# Esquematico.net
KiCad netlist of a schematic drawn in Altium Designer
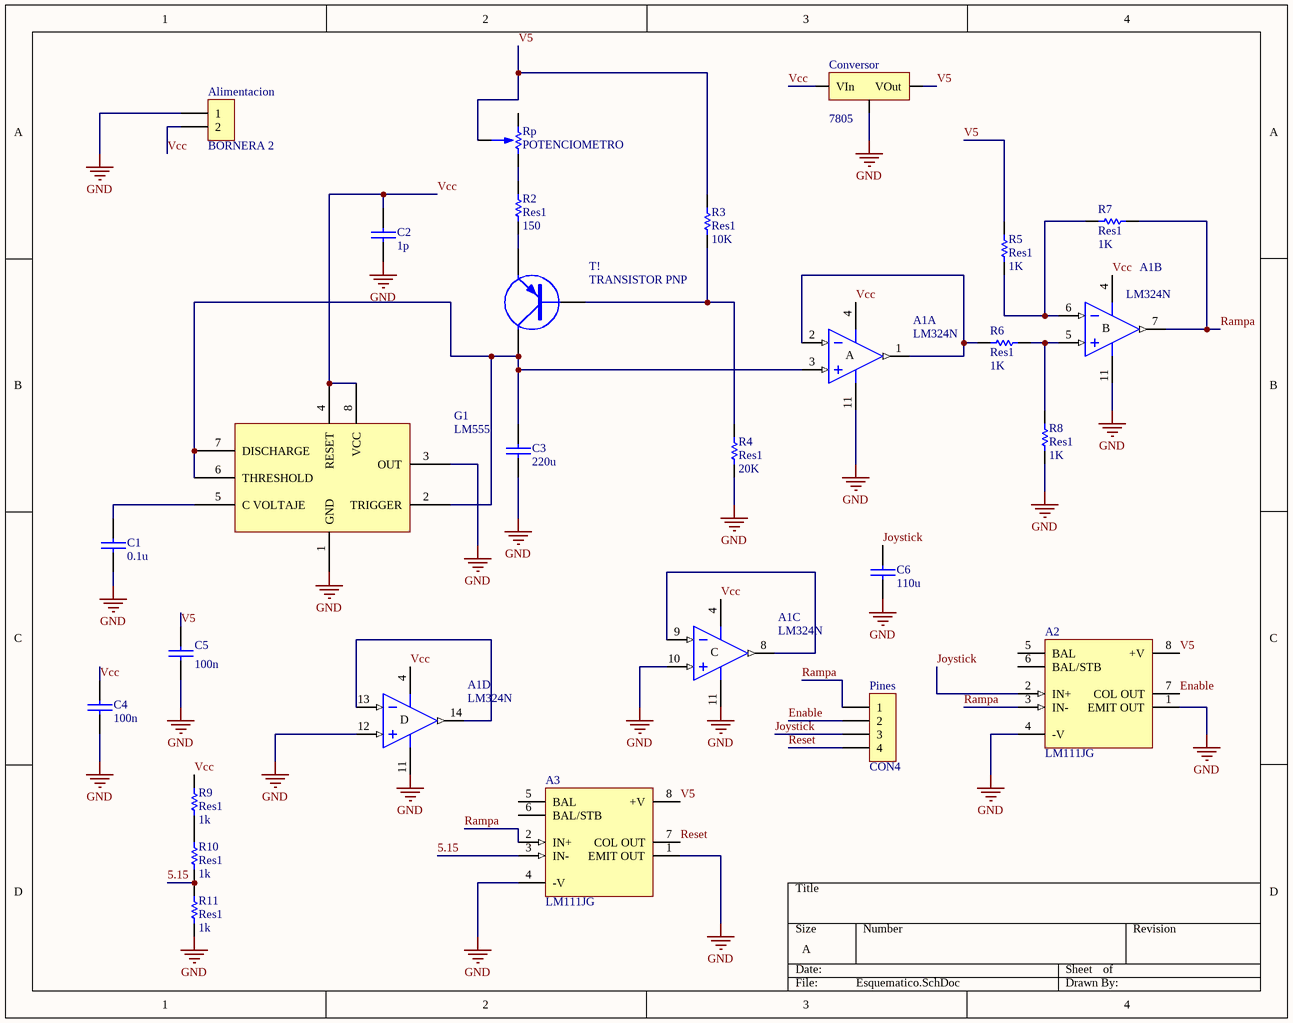
[diagram p0: Esquematico.SchDoc]

(export (version "E")
  (design (tool "Eeschema 10.0.6"))
  (components
    (comp (ref "A1")
      (value "LM324N")
      (footprint "N014")
      (description "Quadruple Operational Amplifier")
      (fields (field (name "PUBLISHER") "Altium Limited"))
      (libsource (lib "TI Operational Amplifier") (part "LM324N"))
    )
    (comp (ref "A2")
      (value "LM111JG")
      (footprint "JG008")
      (description "Differential Comparator with Strobe")
      (fields (field (name "PUBLISHER") "Altium Limited"))
      (libsource (lib "TI Analog Comparator") (part "LM111JG"))
    )
    (comp (ref "A3")
      (value "LM111JG")
      (footprint "JG008")
      (description "Differential Comparator with Strobe")
      (fields (field (name "PUBLISHER") "Altium Limited"))
      (libsource (lib "TI Analog Comparator") (part "LM111JG"))
    )
    (comp (ref "Alimentacion")
      (value "BORNERA 2")
      (footprint "BORNERA2")
      (libsource (lib "LIBEBAL") (part "BORNERA 2"))
    )
    (comp (ref "C1") (value "0.1u") (footprint "CAP100") (libsource (lib "LIBEBAL") (part "CAP")))
    (comp (ref "C2") (value "1p") (footprint "CAP100") (libsource (lib "LIBEBAL") (part "CAP")))
    (comp (ref "C3") (value "220u") (footprint "CAP100") (libsource (lib "LIBEBAL") (part "CAP")))
    (comp (ref "C4") (value "100n") (footprint "CAP100") (libsource (lib "LIBEBAL") (part "CAP")))
    (comp (ref "C5") (value "100n") (footprint "CAP100") (libsource (lib "LIBEBAL") (part "CAP")))
    (comp (ref "C6") (value "110u") (footprint "CAP100") (libsource (lib "LIBEBAL") (part "CAP")))
    (comp (ref "Conversor")
      (value "7805")
      (footprint "TO-220 V")
      (description "REGULDOR POSITIVO")
      (libsource (lib "LIBEBAL") (part "78XX"))
    )
    (comp (ref "G1")
      (value "LM555")
      (footprint "DIP8")
      (description "Timer")
      (libsource (lib "LIBEBAL") (part "LM555"))
    )
    (comp (ref "Pines") (value "CON4") (footprint "SIP4") (libsource (lib "LIBEBAL") (part "CON4")))
    (comp (ref "R2")
      (value "Res1")
      (footprint "AXIAL-0.3")
      (description "Resistor")
      (fields (field (name "ALTIUM_VALUE") "150") (field (name "PUBLISHER") "Altium Limited"))
      (libsource (lib "Miscellaneous Devices") (part "Res1"))
    )
    (comp (ref "R3")
      (value "Res1")
      (footprint "AXIAL-0.3")
      (description "Resistor")
      (fields (field (name "ALTIUM_VALUE") "10K") (field (name "PUBLISHER") "Altium Limited"))
      (libsource (lib "Miscellaneous Devices") (part "Res1"))
    )
    (comp (ref "R4")
      (value "Res1")
      (footprint "AXIAL-0.3")
      (description "Resistor")
      (fields (field (name "ALTIUM_VALUE") "20K") (field (name "PUBLISHER") "Altium Limited"))
      (libsource (lib "Miscellaneous Devices") (part "Res1"))
    )
    (comp (ref "R5")
      (value "Res1")
      (footprint "AXIAL-0.3")
      (description "Resistor")
      (fields (field (name "ALTIUM_VALUE") "1K") (field (name "PUBLISHER") "Altium Limited"))
      (libsource (lib "Miscellaneous Devices") (part "Res1"))
    )
    (comp (ref "R6")
      (value "Res1")
      (footprint "AXIAL-0.3")
      (description "Resistor")
      (fields (field (name "ALTIUM_VALUE") "1K") (field (name "PUBLISHER") "Altium Limited"))
      (libsource (lib "Miscellaneous Devices") (part "Res1"))
    )
    (comp (ref "R7")
      (value "Res1")
      (footprint "AXIAL-0.3")
      (description "Resistor")
      (fields (field (name "ALTIUM_VALUE") "1K") (field (name "PUBLISHER") "Altium Limited"))
      (libsource (lib "Miscellaneous Devices") (part "Res1"))
    )
    (comp (ref "R8")
      (value "Res1")
      (footprint "AXIAL-0.3")
      (description "Resistor")
      (fields (field (name "ALTIUM_VALUE") "1K") (field (name "PUBLISHER") "Altium Limited"))
      (libsource (lib "Miscellaneous Devices") (part "Res1"))
    )
    (comp (ref "R9")
      (value "Res1")
      (footprint "AXIAL-0.3")
      (description "Resistor")
      (fields (field (name "ALTIUM_VALUE") "1k") (field (name "PUBLISHER") "Altium Limited"))
      (libsource (lib "Miscellaneous Devices") (part "Res1"))
    )
    (comp (ref "R10")
      (value "Res1")
      (footprint "AXIAL-0.3")
      (description "Resistor")
      (fields (field (name "ALTIUM_VALUE") "1k") (field (name "PUBLISHER") "Altium Limited"))
      (libsource (lib "Miscellaneous Devices") (part "Res1"))
    )
    (comp (ref "R11")
      (value "Res1")
      (footprint "AXIAL-0.3")
      (description "Resistor")
      (fields (field (name "ALTIUM_VALUE") "1k") (field (name "PUBLISHER") "Altium Limited"))
      (libsource (lib "Miscellaneous Devices") (part "Res1"))
    )
    (comp (ref "Rp")
      (value "POTENCIOMETRO")
      (footprint "POTENCIOMETRO")
      (libsource (lib "LIBEBAL") (part "POTENCIOMETRO"))
    )
    (comp (ref "T!")
      (value "TRANSISTOR PNP")
      (footprint "TO92")
      (libsource (lib "LIBEBAL") (part "TRANSISTOR PNP"))
    )
  )
  (nets
    (net (code "1") (name "/5.15") (class "Default")
      (node (ref "A3") (pin "3") (pinfunction "IN-_3") (pintype "input"))
      (node (ref "R10") (pin "1") (pinfunction "1_1") (pintype "passive"))
      (node (ref "R11") (pin "2") (pinfunction "2_2") (pintype "passive"))
    )
    (net (code "2") (name "/Enable") (class "Default")
      (node (ref "A2") (pin "7") (pinfunction "COL_OUT_7") (pintype "open_collector"))
      (node (ref "Pines") (pin "2") (pinfunction "2_2") (pintype "passive"))
    )
    (net (code "3") (name "/Joystick") (class "Default")
      (node (ref "A2") (pin "2") (pinfunction "IN+_2") (pintype "input"))
      (node (ref "C6") (pin "1") (pinfunction "1_1") (pintype "passive"))
      (node (ref "Pines") (pin "3") (pinfunction "3_3") (pintype "passive"))
    )
    (net (code "4") (name "/Rampa") (class "Default")
      (node (ref "A1") (pin "7") (pinfunction "OUT_7") (pintype "output"))
      (node (ref "A2") (pin "3") (pinfunction "IN-_3") (pintype "input"))
      (node (ref "A3") (pin "2") (pinfunction "IN+_2") (pintype "input"))
      (node (ref "Pines") (pin "1") (pinfunction "1_1") (pintype "passive"))
      (node (ref "R7") (pin "1") (pinfunction "1_1") (pintype "passive"))
    )
    (net (code "5") (name "/Reset") (class "Default")
      (node (ref "A3") (pin "7") (pinfunction "COL_OUT_7") (pintype "open_collector"))
      (node (ref "Pines") (pin "4") (pinfunction "4_4") (pintype "passive"))
    )
    (net (code "6") (name "/V5") (class "Default")
      (node (ref "A2") (pin "8") (pinfunction "+V_8") (pintype "power_in"))
      (node (ref "A3") (pin "8") (pinfunction "+V_8") (pintype "power_in"))
      (node (ref "C5") (pin "1") (pinfunction "1_1") (pintype "passive"))
      (node (ref "Conversor") (pin "3") (pinfunction "VOut_3") (pintype "passive"))
      (node (ref "R3") (pin "2") (pinfunction "2_2") (pintype "passive"))
      (node (ref "R5") (pin "2") (pinfunction "2_2") (pintype "passive"))
      (node (ref "Rp") (pin "2") (pinfunction "2_2") (pintype "passive"))
    )
    (net (code "7") (name "/Vcc") (class "Default")
      (node (ref "A1") (pin "4") (pinfunction "V+_4") (pintype "power_in"))
      (node (ref "Alimentacion") (pin "2") (pinfunction "2_2") (pintype "passive"))
      (node (ref "C2") (pin "1") (pinfunction "1_1") (pintype "passive"))
      (node (ref "C4") (pin "1") (pinfunction "1_1") (pintype "passive"))
      (node (ref "Conversor") (pin "1") (pinfunction "VIn_1") (pintype "passive"))
      (node (ref "G1") (pin "4") (pinfunction "RESET_4") (pintype "passive"))
      (node (ref "G1") (pin "8") (pinfunction "VCC_8") (pintype "passive"))
      (node (ref "R9") (pin "2") (pinfunction "2_2") (pintype "passive"))
    )
    (net (code "8") (name "GND") (class "Default")
      (node (ref "A1") (pin "10") (pinfunction "IN+_10") (pintype "input"))
      (node (ref "A1") (pin "11") (pinfunction "V-_11") (pintype "power_in"))
      (node (ref "A1") (pin "12") (pinfunction "IN+_12") (pintype "input"))
      (node (ref "A2") (pin "1") (pinfunction "EMIT_OUT_1") (pintype "open_emitter"))
      (node (ref "A2") (pin "4") (pinfunction "-V_4") (pintype "power_in"))
      (node (ref "A3") (pin "1") (pinfunction "EMIT_OUT_1") (pintype "open_emitter"))
      (node (ref "A3") (pin "4") (pinfunction "-V_4") (pintype "power_in"))
      (node (ref "Alimentacion") (pin "1") (pinfunction "1_1") (pintype "passive"))
      (node (ref "C1") (pin "2") (pinfunction "2_2") (pintype "passive"))
      (node (ref "C2") (pin "2") (pinfunction "2_2") (pintype "passive"))
      (node (ref "C3") (pin "2") (pinfunction "2_2") (pintype "passive"))
      (node (ref "C4") (pin "2") (pinfunction "2_2") (pintype "passive"))
      (node (ref "C5") (pin "2") (pinfunction "2_2") (pintype "passive"))
      (node (ref "C6") (pin "2") (pinfunction "2_2") (pintype "passive"))
      (node (ref "Conversor") (pin "2") (pinfunction "GND_2") (pintype "passive"))
      (node (ref "G1") (pin "1") (pinfunction "GND_1") (pintype "passive"))
      (node (ref "G1") (pin "3") (pinfunction "OUT_3") (pintype "passive"))
      (node (ref "R11") (pin "1") (pinfunction "1_1") (pintype "passive"))
      (node (ref "R4") (pin "1") (pinfunction "1_1") (pintype "passive"))
      (node (ref "R8") (pin "1") (pinfunction "1_1") (pintype "passive"))
    )
    (net (code "9") (name "Net-(A1A-IN+)") (class "Default")
      (node (ref "A1") (pin "3") (pinfunction "IN+_3") (pintype "input"))
      (node (ref "C3") (pin "1") (pinfunction "1_1") (pintype "passive"))
      (node (ref "G1") (pin "2") (pinfunction "TRIGGER_2") (pintype "passive"))
      (node (ref "G1") (pin "6") (pinfunction "THRESHOLD_6") (pintype "passive"))
      (node (ref "G1") (pin "7") (pinfunction "DISCHARGE_7") (pintype "passive"))
      (node (ref "T!") (pin "2") (pinfunction "C_2") (pintype "passive"))
    )
    (net (code "10") (name "Net-(A1A-IN-)") (class "Default")
      (node (ref "A1") (pin "1") (pinfunction "OUT_1") (pintype "output"))
      (node (ref "A1") (pin "2") (pinfunction "IN-_2") (pintype "input"))
      (node (ref "R6") (pin "2") (pinfunction "2_2") (pintype "passive"))
    )
    (net (code "11") (name "Net-(A1B-IN+)") (class "Default")
      (node (ref "A1") (pin "5") (pinfunction "IN+_5") (pintype "input"))
      (node (ref "R6") (pin "1") (pinfunction "1_1") (pintype "passive"))
      (node (ref "R8") (pin "2") (pinfunction "2_2") (pintype "passive"))
    )
    (net (code "12") (name "Net-(A1B-IN-)") (class "Default")
      (node (ref "A1") (pin "6") (pinfunction "IN-_6") (pintype "input"))
      (node (ref "R5") (pin "1") (pinfunction "1_1") (pintype "passive"))
      (node (ref "R7") (pin "2") (pinfunction "2_2") (pintype "passive"))
    )
    (net (code "13") (name "Net-(A1C-IN-)") (class "Default")
      (node (ref "A1") (pin "8") (pinfunction "OUT_8") (pintype "output"))
      (node (ref "A1") (pin "9") (pinfunction "IN-_9") (pintype "input"))
    )
    (net (code "14") (name "Net-(A1D-IN-)") (class "Default")
      (node (ref "A1") (pin "13") (pinfunction "IN-_13") (pintype "input"))
      (node (ref "A1") (pin "14") (pinfunction "OUT_14") (pintype "output"))
    )
    (net (code "15") (name "Net-(G1-C_VOLTAJE)") (class "Default")
      (node (ref "C1") (pin "1") (pinfunction "1_1") (pintype "passive"))
      (node (ref "G1") (pin "5") (pinfunction "C_VOLTAJE_5") (pintype "passive"))
    )
    (net (code "16") (name "Net-(R2-Pad2)") (class "Default")
      (node (ref "R2") (pin "2") (pinfunction "2_2") (pintype "passive"))
      (node (ref "Rp") (pin "1") (pinfunction "1_1") (pintype "passive"))
    )
    (net (code "17") (name "Net-(R10-Pad2)") (class "Default")
      (node (ref "R10") (pin "2") (pinfunction "2_2") (pintype "passive"))
      (node (ref "R9") (pin "1") (pinfunction "1_1") (pintype "passive"))
    )
    (net (code "18") (name "Net-(T!-B)") (class "Default")
      (node (ref "R3") (pin "1") (pinfunction "1_1") (pintype "passive"))
      (node (ref "R4") (pin "2") (pinfunction "2_2") (pintype "passive"))
      (node (ref "T!") (pin "1") (pinfunction "B_1") (pintype "passive"))
    )
    (net (code "19") (name "Net-(T!-E)") (class "Default")
      (node (ref "R2") (pin "1") (pinfunction "1_1") (pintype "passive"))
      (node (ref "T!") (pin "3") (pinfunction "E_3") (pintype "passive"))
    )
    (net (code "20") (name "unconnected-(A2-BAL-Pad5)") (class "Default")
      (node (ref "A2") (pin "5") (pinfunction "BAL_5") (pintype "passive"))
    )
    (net (code "21") (name "unconnected-(A2-BAL{slash}STB-Pad6)") (class "Default")
      (node (ref "A2") (pin "6") (pinfunction "BAL/STB_6") (pintype "passive"))
    )
    (net (code "22") (name "unconnected-(A3-BAL-Pad5)") (class "Default")
      (node (ref "A3") (pin "5") (pinfunction "BAL_5") (pintype "passive"))
    )
    (net (code "23") (name "unconnected-(A3-BAL{slash}STB-Pad6)") (class "Default")
      (node (ref "A3") (pin "6") (pinfunction "BAL/STB_6") (pintype "passive"))
    )
    (net (code "24") (name "unconnected-(Rp-Pad3)") (class "Default")
      (node (ref "Rp") (pin "3") (pinfunction "3_3") (pintype "passive"))
    )
  )
)
